# SOM_Analog_USB.net
KiCad netlist of a schematic drawn in Altium Designer
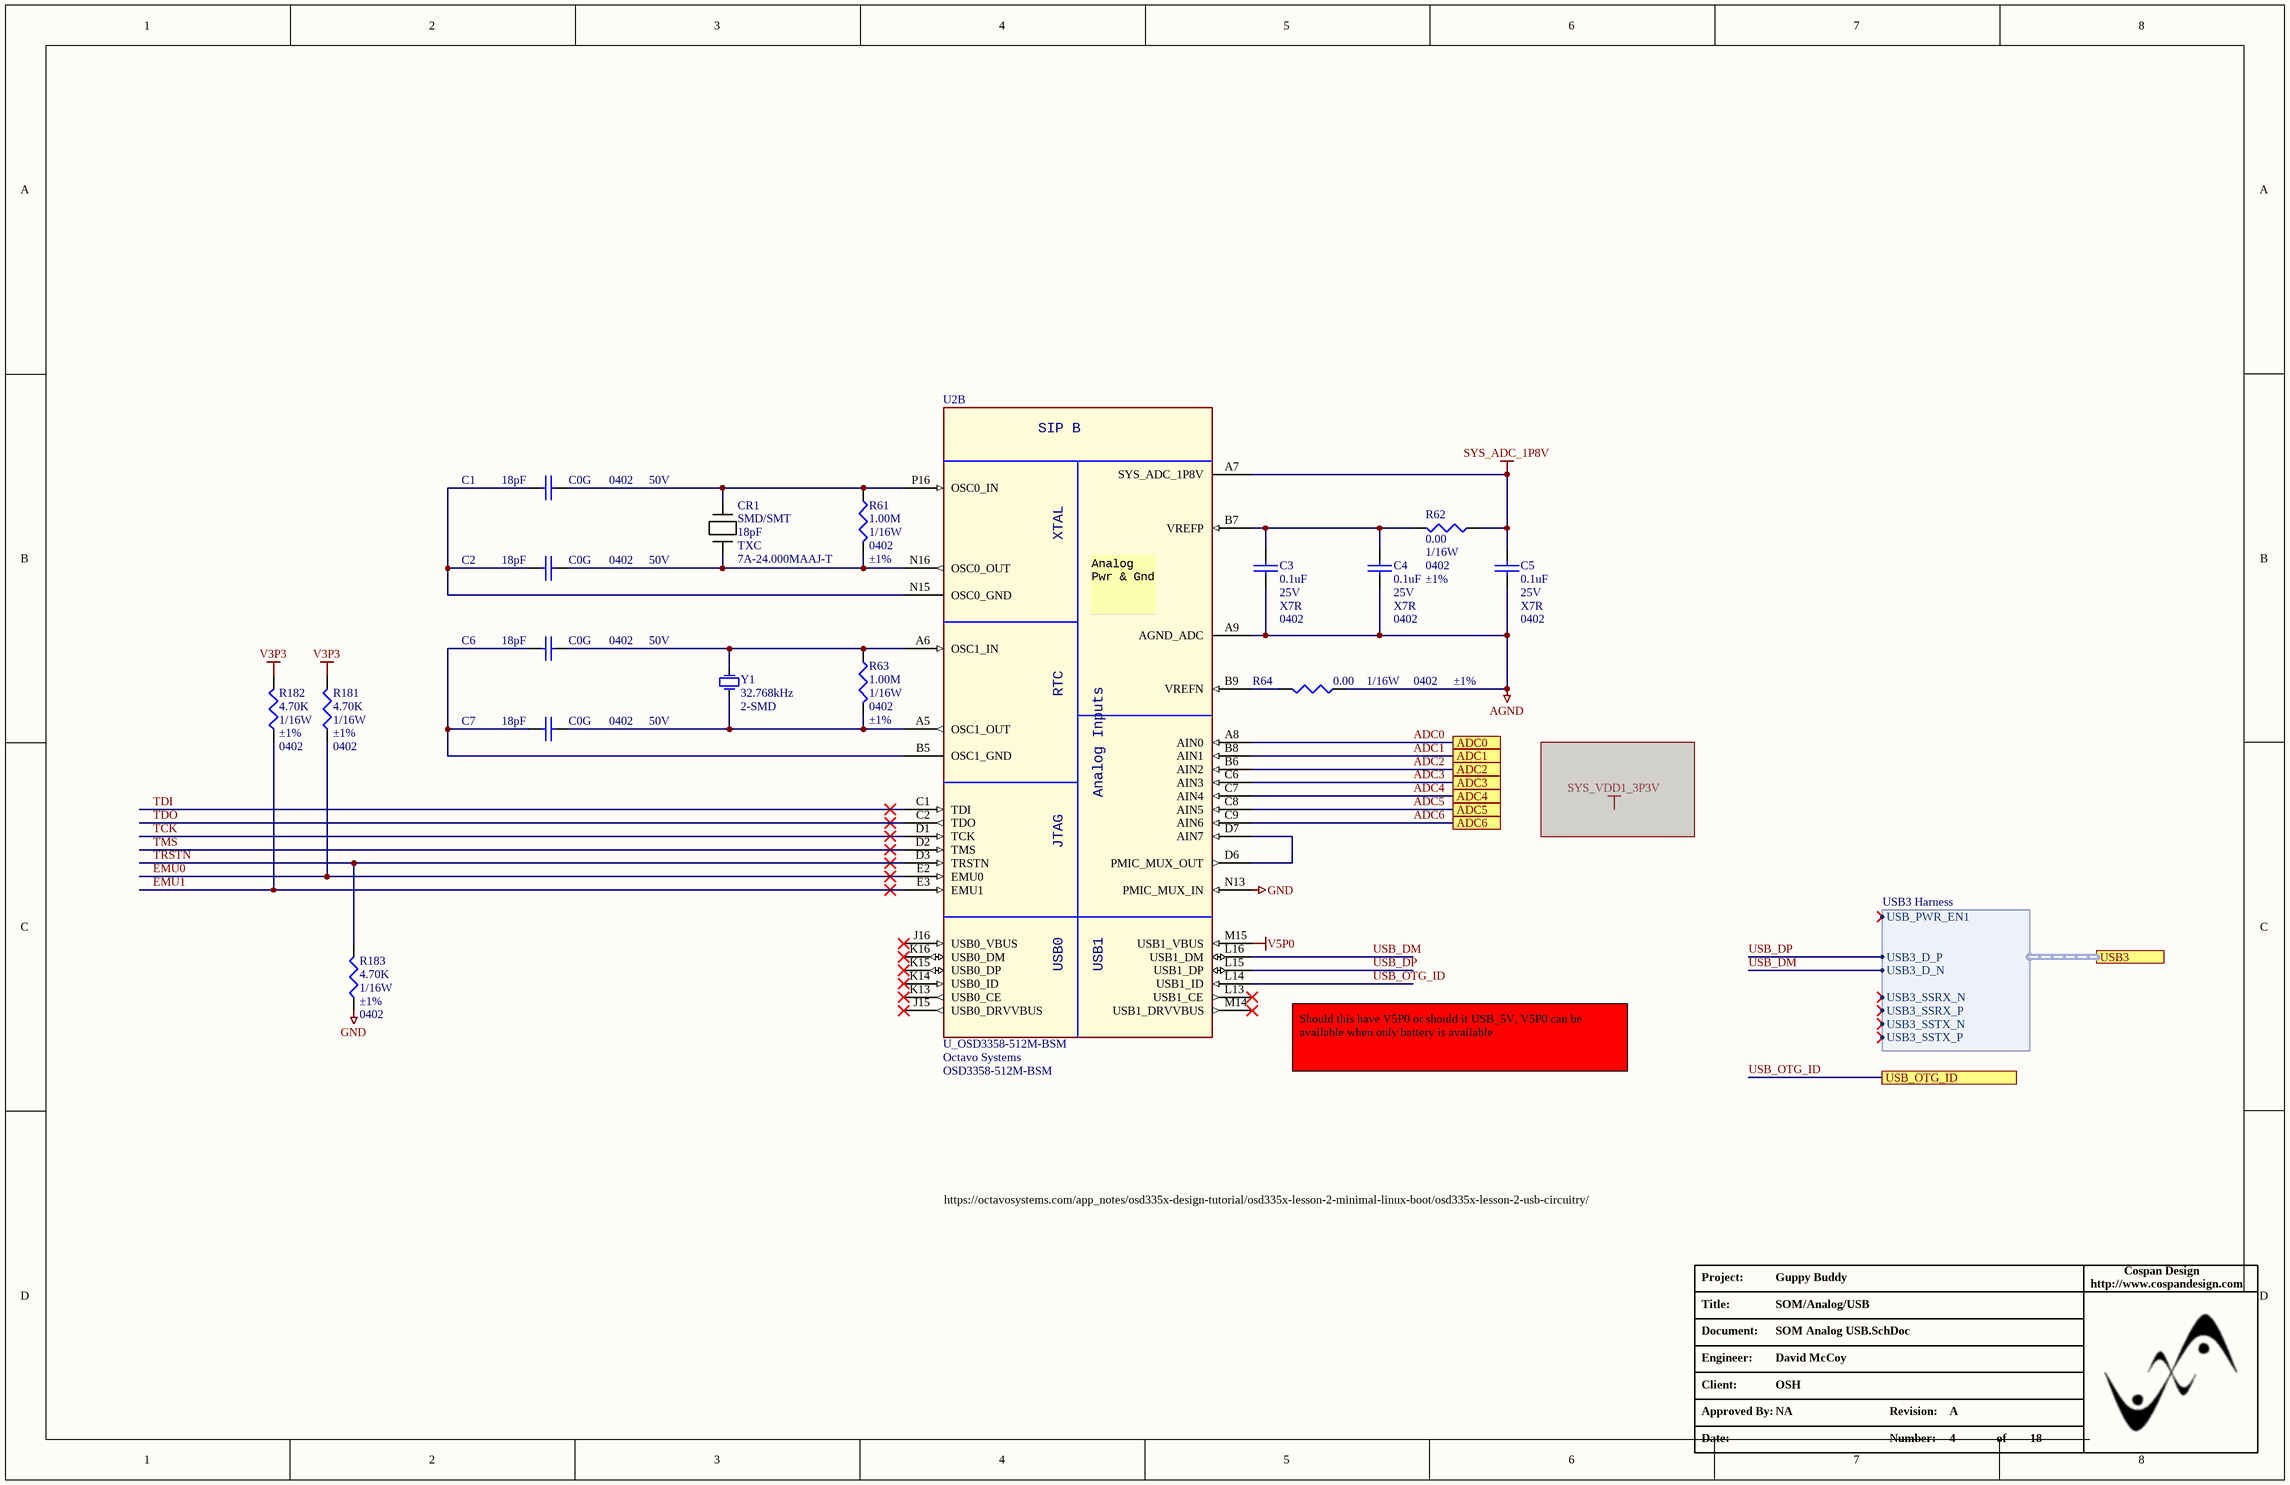
[diagram p0: SOM Analog USB.SchDoc]

(export (version "E")
  (design (tool "Eeschema 10.0.6"))
  (components
    (comp (ref "C1")
      (value "C_0402_18PF_50V")
      (footprint "C_0402")
      (fields
        (field (name "CAPACITANCE") "18pF")
        (field (name "TOLERANCE") "5%")
        (field (name "DIELECTRIC") "C0G")
        (field (name "CASE CODE (IMPERIAL)") "0402")
        (field (name "VOLTAGE RATING") "50V")
      )
      (libsource (lib "Cospan Design") (part "C_0402_18PF_50V"))
    )
    (comp (ref "C2")
      (value "C_0402_18PF_50V")
      (footprint "C_0402")
      (fields
        (field (name "CAPACITANCE") "18pF")
        (field (name "TOLERANCE") "5%")
        (field (name "DIELECTRIC") "C0G")
        (field (name "CASE CODE (IMPERIAL)") "0402")
        (field (name "VOLTAGE RATING") "50V")
      )
      (libsource (lib "Cospan Design") (part "C_0402_18PF_50V"))
    )
    (comp (ref "C3")
      (value "C_0402_0.1UF_25V")
      (footprint "C_0402")
      (description "CAP CER 0.1UF 25V X6S 0402")
      (fields
        (field (name "TOLERANCE") "10%")
        (field (name "CAPACITANCE") "0.1uF")
        (field (name "VOLTAGE - RATED") "25V")
        (field (name "TEMPERATURE COEFFICIENT") "X7R")
        (field (name "PACKAGE / CASE") "0402")
      )
      (libsource (lib "Cospan Design") (part "C_0402_0.1UF_25V"))
    )
    (comp (ref "C4")
      (value "C_0402_0.1UF_25V")
      (footprint "C_0402")
      (description "CAP CER 0.1UF 25V X6S 0402")
      (fields
        (field (name "TOLERANCE") "10%")
        (field (name "CAPACITANCE") "0.1uF")
        (field (name "VOLTAGE - RATED") "25V")
        (field (name "TEMPERATURE COEFFICIENT") "X7R")
        (field (name "PACKAGE / CASE") "0402")
      )
      (libsource (lib "Cospan Design") (part "C_0402_0.1UF_25V"))
    )
    (comp (ref "C5")
      (value "C_0402_0.1UF_25V")
      (footprint "C_0402")
      (description "CAP CER 0.1UF 25V X6S 0402")
      (fields
        (field (name "TOLERANCE") "10%")
        (field (name "CAPACITANCE") "0.1uF")
        (field (name "VOLTAGE - RATED") "25V")
        (field (name "TEMPERATURE COEFFICIENT") "X7R")
        (field (name "PACKAGE / CASE") "0402")
      )
      (libsource (lib "Cospan Design") (part "C_0402_0.1UF_25V"))
    )
    (comp (ref "C6")
      (value "C_0402_18PF_50V")
      (footprint "C_0402")
      (fields
        (field (name "CAPACITANCE") "18pF")
        (field (name "TOLERANCE") "5%")
        (field (name "DIELECTRIC") "C0G")
        (field (name "CASE CODE (IMPERIAL)") "0402")
        (field (name "VOLTAGE RATING") "50V")
      )
      (libsource (lib "Cospan Design") (part "C_0402_18PF_50V"))
    )
    (comp (ref "C7")
      (value "C_0402_18PF_50V")
      (footprint "C_0402")
      (fields
        (field (name "CAPACITANCE") "18pF")
        (field (name "TOLERANCE") "5%")
        (field (name "DIELECTRIC") "C0G")
        (field (name "CASE CODE (IMPERIAL)") "0402")
        (field (name "VOLTAGE RATING") "50V")
      )
      (libsource (lib "Cospan Design") (part "C_0402_18PF_50V"))
    )
    (comp (ref "CR1")
      (value "Y_7A-24.000MAAJ-T")
      (footprint "CRYSTAL_TXC_7A")
      (description "Imported")
      (fields
        (field (name "MANUFACTURER_PART_NUMBER") "7A-24.000MAAJ-T")
        (field (name "TOLERANCE") "30ppm")
        (field (name "CASE/PACKAGE") "SMD/SMT")
        (field (name "LOAD CAPACITANCE") "18pF")
        (field (name "MANUFACTURER 1") "TXC")
        (field (name "MANUFACTURER PART NUMBER 1") "7A-24.000MAAJ-T")
      )
      (libsource (lib "Cospan Design") (part "Y_7A-24.000MAAJ-T"))
    )
    (comp (ref "R61")
      (value "1.0M Ohms")
      (footprint "R_0402")
      (description "RES 1.00M OHM 1/16W 1% 0402 SMD")
      (fields
        (field (name "MANUFACTURER") "Vishay/Dale")
        (field (name "MANUFACTURER PART NUMBER") "CRCW04021M00FKED")
        (field (name "RESISTANCE IN OHMS") "1.00M")
        (field (name "POWER (WATTS)") "1/16W")
        (field (name "CASE") "0402")
        (field (name "TOLERANCE") "±1%")
      )
      (libsource (lib "Main Library") (part "R_0402_1.0M"))
    )
    (comp (ref "R62")
      (value "0.0 Ohms")
      (footprint "R_0402")
      (description "RES 0.00 OHM 1/16W 1% 0402 SMD")
      (fields
        (field (name "MANUFACTURER") "Yageo")
        (field (name "MANUFACTURER PART NUMBER") "RC0402JR-070RL")
        (field (name "RESISTANCE IN OHMS") "0.00")
        (field (name "POWER (WATTS)") "1/16W")
        (field (name "CASE") "0402")
        (field (name "TOLERANCE") "±1%")
      )
      (libsource (lib "Cospan Design") (part "R_0402_0.00"))
    )
    (comp (ref "R63")
      (value "1.0M Ohms")
      (footprint "R_0402")
      (description "RES 1.00M OHM 1/16W 1% 0402 SMD")
      (fields
        (field (name "MANUFACTURER") "Vishay/Dale")
        (field (name "MANUFACTURER PART NUMBER") "CRCW04021M00FKED")
        (field (name "RESISTANCE IN OHMS") "1.00M")
        (field (name "POWER (WATTS)") "1/16W")
        (field (name "CASE") "0402")
        (field (name "TOLERANCE") "±1%")
      )
      (libsource (lib "Main Library") (part "R_0402_1.0M"))
    )
    (comp (ref "R64")
      (value "0.0 Ohms")
      (footprint "R_0402")
      (description "RES 0.00 OHM 1/16W 1% 0402 SMD")
      (fields
        (field (name "MANUFACTURER") "Yageo")
        (field (name "MANUFACTURER PART NUMBER") "RC0402JR-070RL")
        (field (name "RESISTANCE IN OHMS") "0.00")
        (field (name "POWER (WATTS)") "1/16W")
        (field (name "CASE") "0402")
        (field (name "TOLERANCE") "±1%")
      )
      (libsource (lib "Cospan Design") (part "R_0402_0.00"))
    )
    (comp (ref "R181")
      (value "4.7k Ohms")
      (footprint "R_0402")
      (description "RES 4.70K OHM 1/16W 1% 0402 SMD")
      (fields
        (field (name "MANUFACTURER") "Yageo")
        (field (name "MANUFACTURER PART NUMBER") "RC0402FR-074K7L")
        (field (name "RESISTANCE IN OHMS") "4.70K")
        (field (name "POWER (WATTS)") "1/16W")
        (field (name "TOLERANCE") "±1%")
        (field (name "CASE") "0402")
      )
      (libsource (lib "Main Library") (part "R_0402_4.70K"))
    )
    (comp (ref "R182")
      (value "4.7k Ohms")
      (footprint "R_0402")
      (description "RES 4.70K OHM 1/16W 1% 0402 SMD")
      (fields
        (field (name "MANUFACTURER") "Yageo")
        (field (name "MANUFACTURER PART NUMBER") "RC0402FR-074K7L")
        (field (name "RESISTANCE IN OHMS") "4.70K")
        (field (name "POWER (WATTS)") "1/16W")
        (field (name "TOLERANCE") "±1%")
        (field (name "CASE") "0402")
      )
      (libsource (lib "Main Library") (part "R_0402_4.70K"))
    )
    (comp (ref "R183")
      (value "4.7k Ohms")
      (footprint "R_0402")
      (description "RES 4.70K OHM 1/16W 1% 0402 SMD")
      (fields
        (field (name "MANUFACTURER") "Yageo")
        (field (name "MANUFACTURER PART NUMBER") "RC0402FR-074K7L")
        (field (name "RESISTANCE IN OHMS") "4.70K")
        (field (name "POWER (WATTS)") "1/16W")
        (field (name "TOLERANCE") "±1%")
        (field (name "CASE") "0402")
      )
      (libsource (lib "Main Library") (part "R_0402_4.70K"))
    )
    (comp (ref "U2")
      (value "U_OSD3358-512M-BSM")
      (footprint "OSD335X-BGA-256")
      (fields
        (field (name "MANUFACTURER 1") "Octavo Systems")
        (field (name "MANUFACTURER PART NUMBER 1") "OSD3358-512M-BSM")
      )
      (libsource (lib "Cospan Design") (part "U_OSD3358-512M-BSM"))
    )
    (comp (ref "Y1")
      (value "32.768kHz (Tuning Fork)")
      (footprint "FC-135_CRYSTAL")
      (description "CRYSTAL 32.7680KHZ 12.5PF SMD")
      (fields
        (field (name "MANUFACTURER") "Epson Toyocom Corporation")
        (field (name "MANUFACTURER PART NUMBER") "FC-135 32.7680KA-A3")
        (field (name "FREQUENCY") "32.768kHz")
        (field (name "PACKAGE / CASE") "2-SMD")
      )
      (libsource (lib "Main Library") (part "Y_SMD_32KHZ"))
    )
  )
  (nets
    (net (code "3") (name "/ADC0") (class "Default")
      (node (ref "U2") (pin "A8") (pinfunction "AIN0_A8") (pintype "input"))
    )
    (net (code "4") (name "/ADC1") (class "Default")
      (node (ref "U2") (pin "B8") (pinfunction "AIN1_B8") (pintype "input"))
    )
    (net (code "5") (name "/ADC2") (class "Default")
      (node (ref "U2") (pin "B6") (pinfunction "AIN2_B6") (pintype "input"))
    )
    (net (code "6") (name "/ADC3") (class "Default")
      (node (ref "U2") (pin "C6") (pinfunction "AIN3_C6") (pintype "input"))
    )
    (net (code "7") (name "/ADC4") (class "Default")
      (node (ref "U2") (pin "C7") (pinfunction "AIN4_C7") (pintype "input"))
    )
    (net (code "8") (name "/ADC5") (class "Default")
      (node (ref "U2") (pin "C8") (pinfunction "AIN5_C8") (pintype "input"))
    )
    (net (code "9") (name "/ADC6") (class "Default")
      (node (ref "U2") (pin "C9") (pinfunction "AIN6_C9") (pintype "input"))
    )
    (net (code "10") (name "/EMU0") (class "Default")
      (node (ref "R181") (pin "2") (pinfunction "2_2") (pintype "passive"))
      (node (ref "U2") (pin "E2") (pinfunction "EMU0_E2") (pintype "input"))
    )
    (net (code "11") (name "/EMU1") (class "Default")
      (node (ref "R182") (pin "2") (pinfunction "2_2") (pintype "passive"))
      (node (ref "U2") (pin "E3") (pinfunction "EMU1_E3") (pintype "input"))
    )
    (net (code "12") (name "/TCK") (class "Default")
      (node (ref "U2") (pin "D1") (pinfunction "TCK_D1") (pintype "input"))
    )
    (net (code "13") (name "/TDI") (class "Default")
      (node (ref "U2") (pin "C1") (pinfunction "TDI_C1") (pintype "input"))
    )
    (net (code "14") (name "/TDO") (class "Default")
      (node (ref "U2") (pin "C2") (pinfunction "TDO_C2") (pintype "output"))
    )
    (net (code "15") (name "/TMS") (class "Default")
      (node (ref "U2") (pin "D2") (pinfunction "TMS_D2") (pintype "input"))
    )
    (net (code "16") (name "/TRSTN") (class "Default")
      (node (ref "R183") (pin "1") (pinfunction "1_1") (pintype "passive"))
      (node (ref "U2") (pin "D3") (pinfunction "TRSTN_D3") (pintype "input"))
    )
    (net (code "17") (name "/USB_DM") (class "Default")
      (node (ref "U2") (pin "L16") (pinfunction "USB1_DM_L16") (pintype "bidirectional"))
    )
    (net (code "18") (name "/USB_DP") (class "Default")
      (node (ref "U2") (pin "L15") (pinfunction "USB1_DP_L15") (pintype "bidirectional"))
    )
    (net (code "19") (name "/USB_OTG_ID") (class "Default")
      (node (ref "U2") (pin "L14") (pinfunction "USB1_ID_L14") (pintype "input"))
    )
    (net (code "21") (name "AGND") (class "Default")
      (node (ref "C3") (pin "1") (pinfunction "1_1") (pintype "passive"))
      (node (ref "C4") (pin "1") (pinfunction "1_1") (pintype "passive"))
      (node (ref "C5") (pin "1") (pinfunction "1_1") (pintype "passive"))
      (node (ref "R64") (pin "2") (pinfunction "2_2") (pintype "passive"))
      (node (ref "U2") (pin "A9") (pinfunction "AGND_ADC_A9") (pintype "power_in"))
    )
    (net (code "22") (name "GND") (class "Default")
      (node (ref "R183") (pin "2") (pinfunction "2_2") (pintype "passive"))
      (node (ref "U2") (pin "N13") (pinfunction "PMIC_MUX_IN_N13") (pintype "input"))
    )
    (net (code "23") (name "Net-(U2B-AIN7)") (class "Default")
      (node (ref "U2") (pin "D6") (pinfunction "PMIC_MUX_OUT_D6") (pintype "output"))
      (node (ref "U2") (pin "D7") (pinfunction "AIN7_D7") (pintype "input"))
    )
    (net (code "24") (name "Net-(U2B-OSC0_GND)") (class "Default")
      (node (ref "C1") (pin "1") (pinfunction "1_1") (pintype "passive"))
      (node (ref "C2") (pin "1") (pinfunction "1_1") (pintype "passive"))
      (node (ref "U2") (pin "N15") (pinfunction "OSC0_GND_N15") (pintype "power_in"))
    )
    (net (code "25") (name "Net-(U2B-OSC0_IN)") (class "Default")
      (node (ref "C1") (pin "2") (pinfunction "2_2") (pintype "passive"))
      (node (ref "CR1") (pin "2") (pinfunction "2_2") (pintype "passive"))
      (node (ref "R61") (pin "2") (pinfunction "2_2") (pintype "passive"))
      (node (ref "U2") (pin "P16") (pinfunction "OSC0_IN_P16") (pintype "input"))
    )
    (net (code "26") (name "Net-(U2B-OSC0_OUT)") (class "Default")
      (node (ref "C2") (pin "2") (pinfunction "2_2") (pintype "passive"))
      (node (ref "CR1") (pin "1") (pinfunction "1_1") (pintype "passive"))
      (node (ref "R61") (pin "1") (pinfunction "1_1") (pintype "passive"))
      (node (ref "U2") (pin "N16") (pinfunction "OSC0_OUT_N16") (pintype "output"))
    )
    (net (code "27") (name "Net-(U2B-OSC1_GND)") (class "Default")
      (node (ref "C6") (pin "1") (pinfunction "1_1") (pintype "passive"))
      (node (ref "C7") (pin "1") (pinfunction "1_1") (pintype "passive"))
      (node (ref "U2") (pin "B5") (pinfunction "OSC1_GND_B5") (pintype "power_in"))
    )
    (net (code "28") (name "Net-(U2B-OSC1_IN)") (class "Default")
      (node (ref "C6") (pin "2") (pinfunction "2_2") (pintype "passive"))
      (node (ref "R63") (pin "2") (pinfunction "2_2") (pintype "passive"))
      (node (ref "U2") (pin "A6") (pinfunction "OSC1_IN_A6") (pintype "input"))
      (node (ref "Y1") (pin "1") (pinfunction "1_1") (pintype "passive"))
    )
    (net (code "29") (name "Net-(U2B-OSC1_OUT)") (class "Default")
      (node (ref "C7") (pin "2") (pinfunction "2_2") (pintype "passive"))
      (node (ref "R63") (pin "1") (pinfunction "1_1") (pintype "passive"))
      (node (ref "U2") (pin "A5") (pinfunction "OSC1_OUT_A5") (pintype "output"))
      (node (ref "Y1") (pin "2") (pinfunction "2_2") (pintype "passive"))
    )
    (net (code "30") (name "Net-(U2B-VREFN)") (class "Default")
      (node (ref "R64") (pin "1") (pinfunction "1_1") (pintype "passive"))
      (node (ref "U2") (pin "B9") (pinfunction "VREFN_B9") (pintype "input"))
    )
    (net (code "31") (name "Net-(U2B-VREFP)") (class "Default")
      (node (ref "C3") (pin "2") (pinfunction "2_2") (pintype "passive"))
      (node (ref "C4") (pin "2") (pinfunction "2_2") (pintype "passive"))
      (node (ref "R62") (pin "1") (pinfunction "1_1") (pintype "passive"))
      (node (ref "U2") (pin "B7") (pinfunction "VREFP_B7") (pintype "input"))
    )
    (net (code "32") (name "SYS_ADC_1P8V") (class "Default")
      (node (ref "C5") (pin "2") (pinfunction "2_2") (pintype "passive"))
      (node (ref "R62") (pin "2") (pinfunction "2_2") (pintype "passive"))
      (node (ref "U2") (pin "A7") (pinfunction "SYS_ADC_1P8V_A7") (pintype "power_in"))
    )
    (net (code "34") (name "V3P3") (class "Default")
      (node (ref "R181") (pin "1") (pinfunction "1_1") (pintype "passive"))
      (node (ref "R182") (pin "1") (pinfunction "1_1") (pintype "passive"))
    )
    (net (code "35") (name "V5P0") (class "Default")
      (node (ref "U2") (pin "M15") (pinfunction "USB1_VBUS_M15") (pintype "input"))
    )
    (net (code "36") (name "unconnected-(U2B-USB0_CE-PadK13)") (class "Default")
      (node (ref "U2") (pin "K13") (pinfunction "USB0_CE_K13") (pintype "output+no_connect"))
    )
    (net (code "37") (name "unconnected-(U2B-USB0_DM-PadK16)") (class "Default")
      (node (ref "U2") (pin "K16") (pinfunction "USB0_DM_K16") (pintype "bidirectional+no_connect"))
    )
    (net (code "38") (name "unconnected-(U2B-USB0_DP-PadK15)") (class "Default")
      (node (ref "U2") (pin "K15") (pinfunction "USB0_DP_K15") (pintype "bidirectional+no_connect"))
    )
    (net (code "39") (name "unconnected-(U2B-USB0_DRVVBUS-PadJ15)") (class "Default")
      (node (ref "U2") (pin "J15") (pinfunction "USB0_DRVVBUS_J15") (pintype "output+no_connect"))
    )
    (net (code "40") (name "unconnected-(U2B-USB0_ID-PadK14)") (class "Default")
      (node (ref "U2") (pin "K14") (pinfunction "USB0_ID_K14") (pintype "input+no_connect"))
    )
    (net (code "41") (name "unconnected-(U2B-USB0_VBUS-PadJ16)") (class "Default")
      (node (ref "U2") (pin "J16") (pinfunction "USB0_VBUS_J16") (pintype "input+no_connect"))
    )
    (net (code "42") (name "unconnected-(U2B-USB1_CE-PadL13)") (class "Default")
      (node (ref "U2") (pin "L13") (pinfunction "USB1_CE_L13") (pintype "output+no_connect"))
    )
    (net (code "43") (name "unconnected-(U2B-USB1_DRVVBUS-PadM14)") (class "Default")
      (node (ref "U2") (pin "M14") (pinfunction "USB1_DRVVBUS_M14") (pintype "output+no_connect"))
    )
  )
)
